# 9.net
KiCad netlist of a schematic drawn in Altium Designer
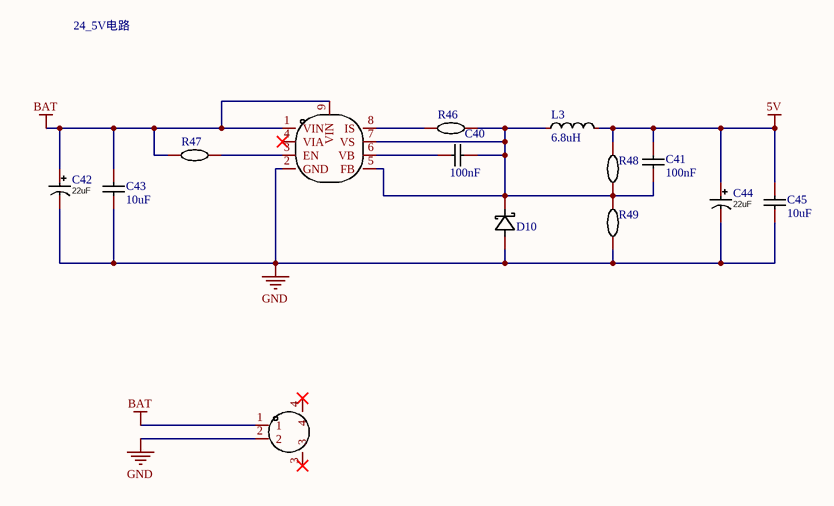
[diagram p0: 9_降压电路.SchDoc]

(export (version "E")
  (design (tool "Eeschema 10.0.6"))
  (components
    (comp (ref "C40")
      (value "100nF")
      (footprint "0603C")
      (fields
        (field (name "MANUFACTURER") "FH")
        (field (name "MANUFACTURER PART") "0603B104K500NT")
        (field (name "NAME") "100nF")
      )
      (libsource (lib "3_C5157152_TP5000移动电源方案验证板.schdoc") (part "0603B104K500NT"))
    )
    (comp (ref "C41")
      (value "100nF")
      (footprint "0603C")
      (fields
        (field (name "MANUFACTURER") "FH")
        (field (name "MANUFACTURER PART") "0603B104K500NT")
        (field (name "NAME") "100nF")
      )
      (libsource (lib "3_C5157152_TP5000移动电源方案验证板.schdoc") (part "0603B104K500NT"))
    )
    (comp (ref "C42")
      (value "22uF")
      (footprint "CAP-SMD_BD6.3-L6.6-W6.6-FD")
      (fields (field (name "MANUFACTURER PART") "CL31A226KAHNNNE"))
      (libsource (lib "3_C5157152_TP5000移动电源方案验证板.schdoc") (part "CL31A226KAHNNNE"))
    )
    (comp (ref "C43")
      (value "10uF")
      (footprint "1206C")
      (fields (field (name "MANUFACTURER PART") "CL31A106KBHNNNE") (field (name "NAME") "10uF"))
      (libsource (lib "3_C5157152_TP5000移动电源方案验证板.schdoc") (part "CL31A106KBHNNNE"))
    )
    (comp (ref "C44")
      (value "22uF")
      (footprint "CAP-SMD_BD6.3-L6.6-W6.6-FD")
      (fields (field (name "MANUFACTURER PART") "CL31A226KAHNNNE"))
      (libsource (lib "3_C5157152_TP5000移动电源方案验证板.schdoc") (part "CL31A226KAHNNNE"))
    )
    (comp (ref "C45")
      (value "10uF")
      (footprint "1206C")
      (fields (field (name "MANUFACTURER PART") "CL31A106KBHNNNE") (field (name "NAME") "10uF"))
      (libsource (lib "3_C5157152_TP5000移动电源方案验证板.schdoc") (part "CL31A106KBHNNNE"))
    )
    (comp (ref "CN8")
      (value "XT30PW-M")
      (footprint "CONN-TH_XT30PW-M")
      (libsource (lib "XT30PW-M1_XT30PW-M.schdoc") (part "XT30PW-M"))
    )
    (comp (ref "D10")
      (value "SS32")
      (footprint "SMAF_L4.3-W2.5-LS5.0-RD")
      (libsource (lib "3_C5157152_TP5000移动电源方案验证板.schdoc") (part "SS32"))
    )
    (comp (ref "L3")
      (value "6.8uH")
      (footprint "IND-SMD_L12.0-W12.0")
      (fields (field (name "MANUFACTURER PART") "SDRH.1207.NLF6R8MT00") (field (name "NAME") "6.8uH"))
      (libsource (lib "3_C5157152_TP5000移动电源方案验证板.schdoc") (part "SDRH.1207.NLF6R8MT00"))
    )
    (comp (ref "R46")
      (value "0603WAF1002T5E")
      (footprint "0603R")
      (fields (field (name "MANUFACTURER") "UniOhm"))
      (libsource (lib "3_C5157152_TP5000移动电源方案验证板.schdoc") (part "0603WAF1002T5E"))
    )
    (comp (ref "R47")
      (value "0603WAF1002T5E")
      (footprint "0603R")
      (fields (field (name "MANUFACTURER") "UniOhm"))
      (libsource (lib "3_C5157152_TP5000移动电源方案验证板.schdoc") (part "0603WAF1002T5E"))
    )
    (comp (ref "R48")
      (value "0603WAF1002T5E")
      (footprint "0603R")
      (fields (field (name "MANUFACTURER") "UniOhm"))
      (libsource (lib "3_C5157152_TP5000移动电源方案验证板.schdoc") (part "0603WAF1002T5E"))
    )
    (comp (ref "R49")
      (value "0603WAF1002T5E")
      (footprint "0603R")
      (fields (field (name "MANUFACTURER") "UniOhm"))
      (libsource (lib "3_C5157152_TP5000移动电源方案验证板.schdoc") (part "0603WAF1002T5E"))
    )
    (comp (ref "U11")
      (value "ICW6208")
      (footprint "ESOP-8_L4.9-W3.9-P1.27-LS6.0-TL-EP3.3")
      (libsource (lib "ICW62081_ICW6208.schdoc") (part "ICW6208"))
    )
  )
  (nets
    (net (code "1") (name "5V") (class "Default")
      (node (ref "C41") (pin "2") (pinfunction "2_2") (pintype "passive"))
      (node (ref "C44") (pin "1") (pinfunction "1_1") (pintype "passive"))
      (node (ref "C45") (pin "2") (pinfunction "2_2") (pintype "passive"))
      (node (ref "L3") (pin "2") (pinfunction "2_2") (pintype "passive"))
      (node (ref "R48") (pin "2") (pinfunction "2_2") (pintype "passive"))
    )
    (net (code "2") (name "BAT") (class "Default")
      (node (ref "C42") (pin "1") (pinfunction "1_1") (pintype "passive"))
      (node (ref "C43") (pin "2") (pinfunction "2_2") (pintype "passive"))
      (node (ref "CN8") (pin "1") (pinfunction "1_1") (pintype "passive"))
      (node (ref "R47") (pin "1") (pinfunction "1_1") (pintype "passive"))
      (node (ref "U11") (pin "1") (pinfunction "VIN_1") (pintype "passive"))
      (node (ref "U11") (pin "9") (pinfunction "VIN_9") (pintype "passive"))
    )
    (net (code "3") (name "GND") (class "Default")
      (node (ref "C42") (pin "2") (pinfunction "2_2") (pintype "passive"))
      (node (ref "C43") (pin "1") (pinfunction "1_1") (pintype "passive"))
      (node (ref "C44") (pin "2") (pinfunction "2_2") (pintype "passive"))
      (node (ref "C45") (pin "1") (pinfunction "1_1") (pintype "passive"))
      (node (ref "CN8") (pin "2") (pinfunction "2_2") (pintype "passive"))
      (node (ref "D10") (pin "2") (pinfunction "A_2") (pintype "passive"))
      (node (ref "R49") (pin "1") (pinfunction "1_1") (pintype "passive"))
      (node (ref "U11") (pin "2") (pinfunction "GND_2") (pintype "passive"))
    )
    (net (code "4") (name "Net-(D10-C)") (class "Default")
      (node (ref "C40") (pin "2") (pinfunction "2_2") (pintype "passive"))
      (node (ref "C41") (pin "1") (pinfunction "1_1") (pintype "passive"))
      (node (ref "D10") (pin "1") (pinfunction "C_1") (pintype "passive"))
      (node (ref "L3") (pin "1") (pinfunction "1_1") (pintype "passive"))
      (node (ref "R46") (pin "2") (pinfunction "2_2") (pintype "passive"))
      (node (ref "R48") (pin "1") (pinfunction "1_1") (pintype "passive"))
      (node (ref "R49") (pin "2") (pinfunction "2_2") (pintype "passive"))
      (node (ref "U11") (pin "5") (pinfunction "FB_5") (pintype "passive"))
      (node (ref "U11") (pin "7") (pinfunction "VS_7") (pintype "passive"))
    )
    (net (code "5") (name "Net-(U11-EN)") (class "Default")
      (node (ref "R47") (pin "2") (pinfunction "2_2") (pintype "passive"))
      (node (ref "U11") (pin "3") (pinfunction "EN_3") (pintype "passive"))
    )
    (net (code "6") (name "Net-(U11-IS)") (class "Default")
      (node (ref "R46") (pin "1") (pinfunction "1_1") (pintype "passive"))
      (node (ref "U11") (pin "8") (pinfunction "IS_8") (pintype "passive"))
    )
    (net (code "7") (name "Net-(U11-VB)") (class "Default")
      (node (ref "C40") (pin "1") (pinfunction "1_1") (pintype "passive"))
      (node (ref "U11") (pin "6") (pinfunction "VB_6") (pintype "passive"))
    )
    (net (code "8") (name "unconnected-(CN8-Pad3)") (class "Default")
      (node (ref "CN8") (pin "3") (pinfunction "3_3") (pintype "passive+no_connect"))
    )
    (net (code "9") (name "unconnected-(CN8-Pad4)") (class "Default")
      (node (ref "CN8") (pin "4") (pinfunction "4_4") (pintype "passive+no_connect"))
    )
    (net (code "10") (name "unconnected-(U11-VIA-Pad4)") (class "Default")
      (node (ref "U11") (pin "4") (pinfunction "VIA_4") (pintype "passive+no_connect"))
    )
  )
)
